# Dongle_charger.net
KiCad netlist of a schematic drawn in EAGLE
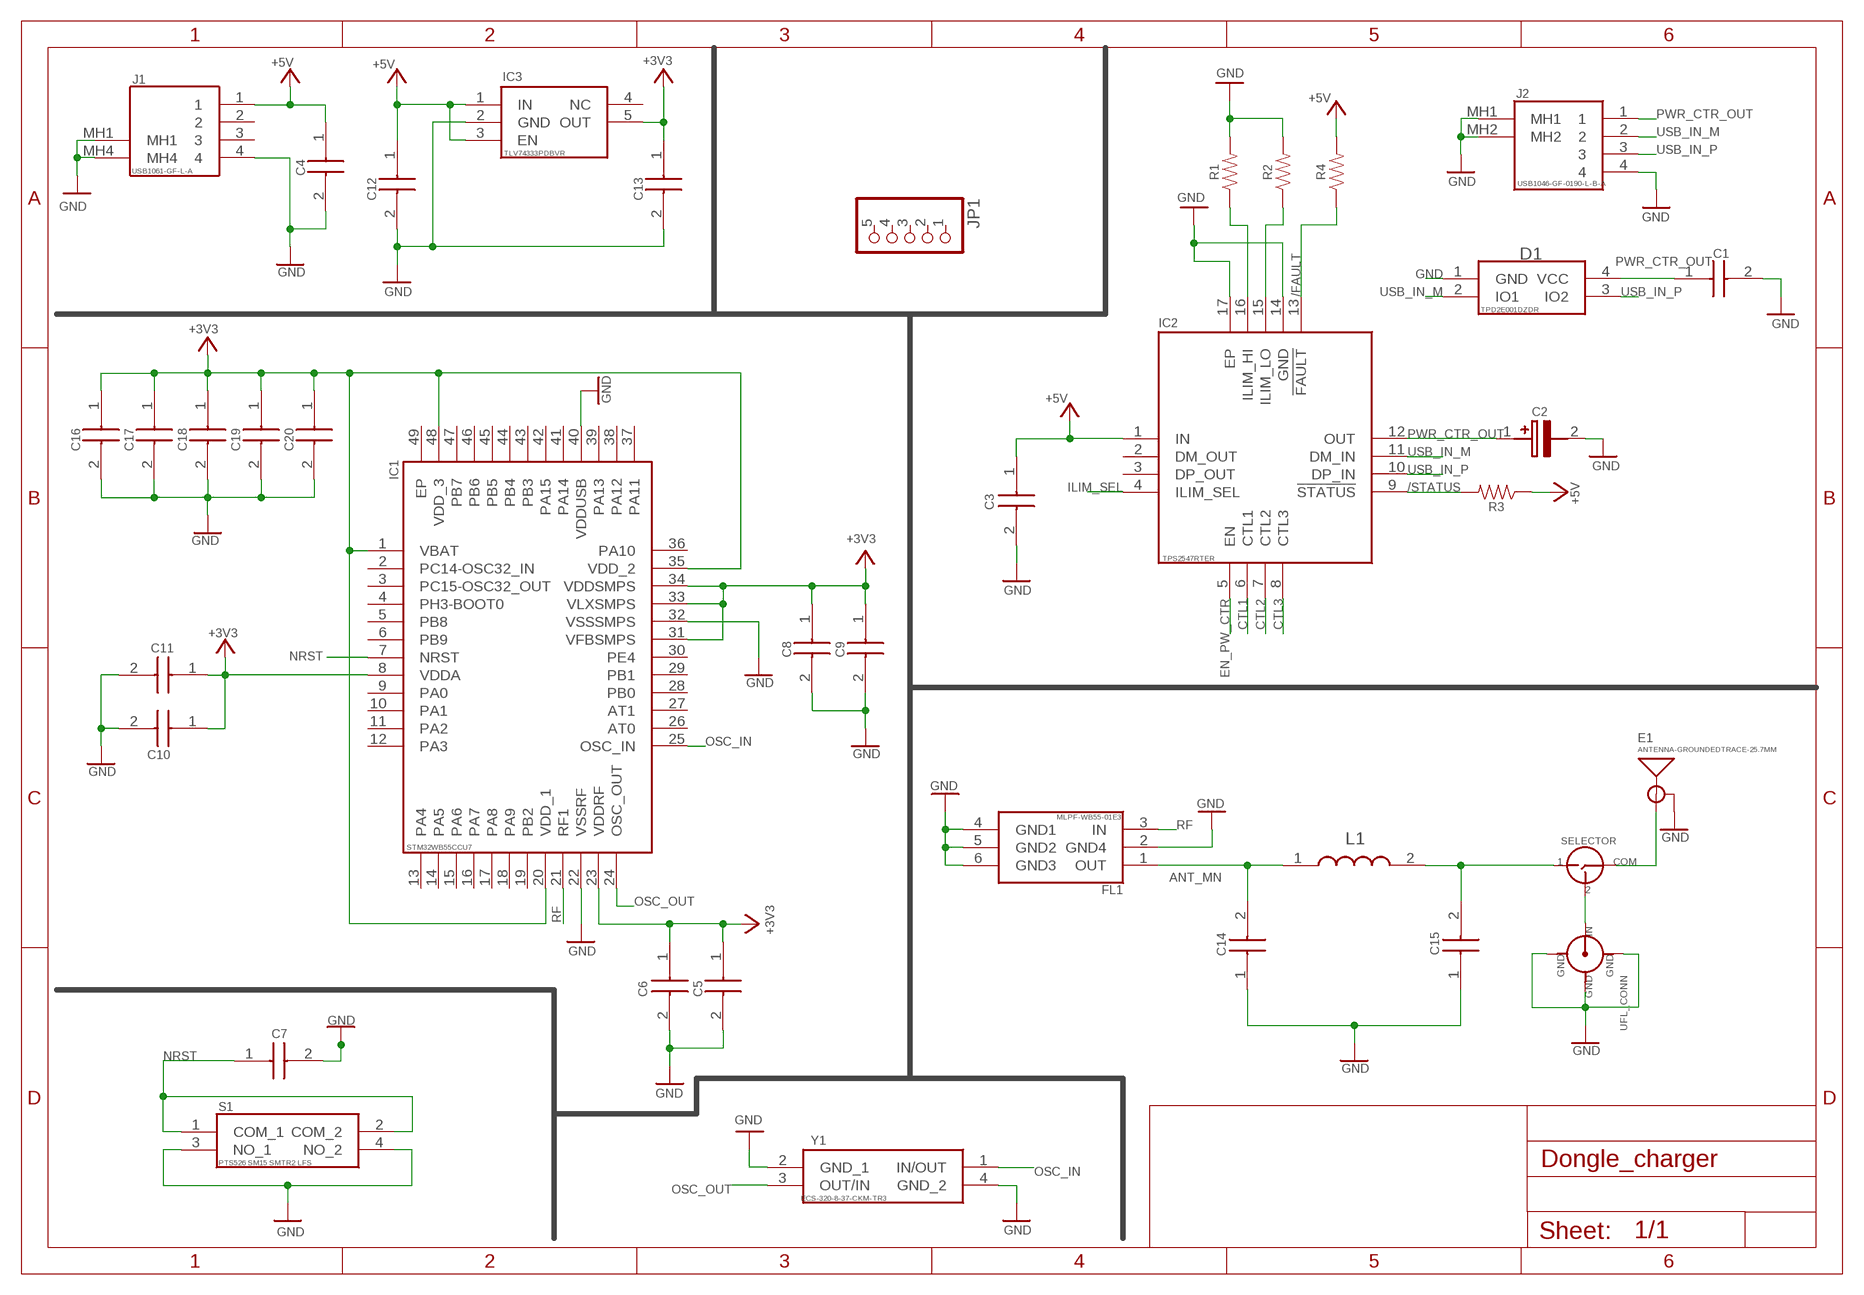
[diagram p0: schematic, sheet 1]

(export (version "E")
  (design (tool "Eeschema 10.0.6"))
  (components
    (comp (ref "C1")
      (value "0.1u")
      (footprint "eagle-import:CAPC1608X95N")
      (fields
        (field (name "MANUFACTURER_PART_NUMBER") "C0603C104K5RAC7867")
        (field (name "MOUSER_PART_NUMBER") "80-C0603C104K5R7867")
      )
      (libsource (lib "eagle-import") (part "C0603C104K5RAC7867"))
    )
    (comp (ref "C2")
      (value "150u")
      (footprint "eagle-import:CAPPM7344X310N")
      (fields (field (name "MANUFACTURER_PART_NUMBER") "TPSD157K010R0100"))
      (libsource (lib "eagle-import") (part "TPSD157K010R0100"))
    )
    (comp (ref "C3")
      (value "0.1u")
      (footprint "eagle-import:CAPC1608X95N")
      (fields
        (field (name "MANUFACTURER_PART_NUMBER") "C0603C104K5RAC7867")
        (field (name "MOUSER_PART_NUMBER") "80-C0603C104K5R7867")
      )
      (libsource (lib "eagle-import") (part "C0603C104K5RAC7867"))
    )
    (comp (ref "C4")
      (value "10u")
      (footprint "eagle-import:CAPC2012X140N")
      (fields
        (field (name "MANUFACTURER_PART_NUMBER") "CL21A106KOQNNNE")
        (field (name "MOUSER_PART_NUMBER") "187-CL21A106KOQNNNE")
      )
      (libsource (lib "eagle-import") (part "CL21A106KOQNNNE"))
    )
    (comp (ref "C5")
      (value "100p")
      (footprint "eagle-import:CAPC1005X55N")
      (fields
        (field (name "MANUFACTURER_PART_NUMBER") "885012205055")
        (field (name "MOUSER_PART_NUMBER") "710-885012205055")
      )
      (libsource (lib "eagle-import") (part "885012205055"))
    )
    (comp (ref "C6")
      (value "100n")
      (footprint "eagle-import:CAPPC1005X55N")
      (fields
        (field (name "MANUFACTURER_PART_NUMBER") "LMF105B7104MVHF")
        (field (name "MOUSER_PART_NUMBER") "963-LMF105B7104MVHF")
      )
      (libsource (lib "eagle-import") (part "LMF105B7104MVHF"))
    )
    (comp (ref "C7")
      (value "C0603C104K5RAC7867")
      (footprint "eagle-import:CAPC1608X95N")
      (fields (field (name "MOUSER_PART_NUMBER") "80-C0603C104K5R7867"))
      (libsource (lib "eagle-import") (part "C0603C104K5RAC7867"))
    )
    (comp (ref "C8")
      (value "4.7u")
      (footprint "eagle-import:CAPC1608X90N")
      (fields
        (field (name "MANUFACTURER_PART_NUMBER") "GRT188R6YA475KE13J")
        (field (name "MOUSER_PART_NUMBER") "81-GRT188R6YA475KE3J")
      )
      (libsource (lib "eagle-import") (part "GRT188R6YA475KE13J"))
    )
    (comp (ref "C9")
      (value "0.1u")
      (footprint "eagle-import:CAPC1608X95N")
      (fields
        (field (name "MANUFACTURER_PART_NUMBER") "C0603C104K5RAC7867")
        (field (name "MOUSER_PART_NUMBER") "80-C0603C104K5R7867")
      )
      (libsource (lib "eagle-import") (part "C0603C104K5RAC7867"))
    )
    (comp (ref "C10")
      (value "10n")
      (footprint "eagle-import:CAPC1608X80N")
      (fields
        (field (name "MANUFACTURER_PART_NUMBER") "C1608X5R1H103K080AA")
        (field (name "MOUSER_PART_NUMBER") "810-C1608X5R1H103KAA")
      )
      (libsource (lib "eagle-import") (part "C1608X5R1H103K080AA"))
    )
    (comp (ref "C11")
      (value "1u")
      (footprint "eagle-import:CAPC1608X90N")
      (fields
        (field (name "MANUFACTURER_PART_NUMBER") "CL10A105KA8NNNC")
        (field (name "MOUSER_PART_NUMBER") "187-CL10A105KA8NNNC")
      )
      (libsource (lib "eagle-import") (part "CL10A105KA8NNNC"))
    )
    (comp (ref "C12")
      (value "1u")
      (footprint "eagle-import:CAPC1608X95N")
      (fields
        (field (name "MANUFACTURER_PART_NUMBER") "C0603C105K3PAC")
        (field (name "MOUSER_PART_NUMBER") "80-C0603C105K3PAC")
      )
      (libsource (lib "eagle-import") (part "C0603C105K3PAC"))
    )
    (comp (ref "C13")
      (value "1u")
      (footprint "eagle-import:CAPC1608X95N")
      (fields
        (field (name "MANUFACTURER_PART_NUMBER") "C0603C105K3PAC")
        (field (name "MOUSER_PART_NUMBER") "80-C0603C105K3PAC")
      )
      (libsource (lib "eagle-import") (part "C0603C105K3PAC"))
    )
    (comp (ref "C14")
      (value "GCM1555G1H1R0CA16D")
      (footprint "eagle-import:CAPC1005X55N")
      (fields (field (name "MOUSER_PART_NUMBER") "81-GCM1555G1H1R0CA6D"))
      (libsource (lib "eagle-import") (part "GCM1555G1H1R0CA16D"))
    )
    (comp (ref "C15")
      (value "GCM1555G1H1R0CA16D")
      (footprint "eagle-import:CAPC1005X55N")
      (fields (field (name "MOUSER_PART_NUMBER") "81-GCM1555G1H1R0CA6D"))
      (libsource (lib "eagle-import") (part "GCM1555G1H1R0CA16D"))
    )
    (comp (ref "C16")
      (value "4.7u")
      (footprint "eagle-import:CAPC1608X90N")
      (fields
        (field (name "MANUFACTURER_PART_NUMBER") "GRT188R6YA475KE13J")
        (field (name "MOUSER_PART_NUMBER") "81-GRT188R6YA475KE3J")
      )
      (libsource (lib "eagle-import") (part "GRT188R6YA475KE13J"))
    )
    (comp (ref "C17")
      (value "0.1u")
      (footprint "eagle-import:CAPC1608X95N")
      (fields
        (field (name "MANUFACTURER_PART_NUMBER") "C0603C104K5RAC7867")
        (field (name "MOUSER_PART_NUMBER") "80-C0603C104K5R7867")
      )
      (libsource (lib "eagle-import") (part "C0603C104K5RAC7867"))
    )
    (comp (ref "C18")
      (value "0.1u")
      (footprint "eagle-import:CAPC1608X95N")
      (fields
        (field (name "MANUFACTURER_PART_NUMBER") "C0603C104K5RAC7867")
        (field (name "MOUSER_PART_NUMBER") "80-C0603C104K5R7867")
      )
      (libsource (lib "eagle-import") (part "C0603C104K5RAC7867"))
    )
    (comp (ref "C19")
      (value "0.1u")
      (footprint "eagle-import:CAPC1608X95N")
      (fields
        (field (name "MANUFACTURER_PART_NUMBER") "C0603C104K5RAC7867")
        (field (name "MOUSER_PART_NUMBER") "80-C0603C104K5R7867")
      )
      (libsource (lib "eagle-import") (part "C0603C104K5RAC7867"))
    )
    (comp (ref "C20")
      (value "0.1u")
      (footprint "eagle-import:CAPC1608X95N")
      (fields
        (field (name "MANUFACTURER_PART_NUMBER") "C0603C104K5RAC7867")
        (field (name "MOUSER_PART_NUMBER") "80-C0603C104K5R7867")
      )
      (libsource (lib "eagle-import") (part "C0603C104K5RAC7867"))
    )
    (comp (ref "D1")
      (value "TPD2E001DZDR")
      (footprint "eagle-import:TPD2E001DZDR")
      (fields
        (field (name "MANUFACTURER_PART_NUMBER") "TPD2E001DZDR")
        (field (name "MOUSER_PART_NUMBER") "595-TPD2E001DZDR")
      )
      (libsource (lib "eagle-import") (part "TPD2E001DZDR"))
    )
    (comp (ref "E1")
      (value "ANTENNA-GROUNDEDTRACE-25.7MM")
      (footprint "eagle-import:TRACE_ANTENNA_2.4GHZ_25.7MM")
      (libsource (lib "eagle-import") (part "ANTENNA-GROUNDEDTRACE-25.7MM"))
    )
    (comp (ref "FL1")
      (value "MLPF-WB55-01E3")
      (footprint "eagle-import:MLPFWB5501E3")
      (fields (field (name "MOUSER_PART_NUMBER") "511-MLPF-WB55-01E3"))
      (libsource (lib "eagle-import") (part "MLPF-WB55-01E3"))
    )
    (comp (ref "IC1")
      (value "STM32WB55CCU7")
      (footprint "eagle-import:QFN50P700X700X65-49N")
      (fields (field (name "MOUSER_PART_NUMBER") "511-STM32WB55CCU7") (field (name "SPICEPREFIX") "X"))
      (libsource (lib "eagle-import") (part "STM32WB55CCU7"))
    )
    (comp (ref "IC2")
      (value "TPS2547RTER")
      (footprint "eagle-import:QFN50P300X300X80-17N")
      (fields
        (field (name "MANUFACTURER_PART_NUMBER") "TPS2547RTER")
        (field (name "MOUSER_PART_NUMBER") "595-TPS2547RTER")
      )
      (libsource (lib "eagle-import") (part "TPS2547RTER"))
    )
    (comp (ref "IC3")
      (value "TLV74333PDBVR")
      (footprint "eagle-import:SOT95P280X145-5N")
      (fields (field (name "MOUSER_PART_NUMBER") "595-TLV74333PDBVR"))
      (libsource (lib "eagle-import") (part "TLV74333PDBVR"))
    )
    (comp (ref "J1")
      (value "USB1061-GF-L-A")
      (footprint "eagle-import:USB1061GFLA")
      (fields
        (field (name "MANUFACTURER_PART_NUMBER") "USB1061-GF-L-A")
        (field (name "MOUSER_PART_NUMBER") "640-USB1061-GF-L-A")
      )
      (libsource (lib "eagle-import") (part "USB1061-GF-L-A"))
    )
    (comp (ref "J2")
      (value "USB1046-GF-0190-L-B-A")
      (footprint "eagle-import:USB1046GF0190LBA")
      (fields
        (field (name "MANUFACTURER_PART_NUMBER") "USB1046-GF-0190-L-B-A")
        (field (name "MOUSER_PART_NUMBER") "640-USB1046GF0190LBA")
      )
      (libsource (lib "eagle-import") (part "USB1046-GF-0190-L-B-A"))
    )
    (comp (ref "JP1")
      (value "PINHD-1X5")
      (footprint "eagle-import:1X05")
      (libsource (lib "eagle-import") (part "PINHD-1X5"))
    )
    (comp (ref "L1")
      (value "ATFC-0402-2N5-BT")
      (footprint "eagle-import:INDC1005X37N")
      (fields (field (name "MOUSER_PART_NUMBER") "815-ATFC-0402-2N5-BT"))
      (libsource (lib "eagle-import") (part "ATFC-0402-2N5-BT"))
    )
    (comp (ref "R1")
      (value "16.9K")
      (footprint "eagle-import:0603")
      (libsource (lib "eagle-import") (part "1.8MOHM"))
    )
    (comp (ref "R2")
      (value "80.6K")
      (footprint "eagle-import:0603")
      (libsource (lib "eagle-import") (part "1.8MOHM"))
    )
    (comp (ref "R3")
      (value "80.6K")
      (footprint "eagle-import:0603")
      (libsource (lib "eagle-import") (part "1.8MOHM"))
    )
    (comp (ref "R4")
      (value "80.6K")
      (footprint "eagle-import:0603")
      (libsource (lib "eagle-import") (part "1.8MOHM"))
    )
    (comp (ref "S1")
      (value "PTS526_SM15_SMTR2_LFS")
      (footprint "eagle-import:PTS526SM15SMTR2LFS")
      (fields
        (field (name "MANUFACTURER_PART_NUMBER") "PTS526 SM15 SMTR2 LFS")
        (field (name "MOUSER_PART_NUMBER") "611-PTS526SM15SMTR2L")
      )
      (libsource (lib "eagle-import") (part "PTS526_SM15_SMTR2_LFS"))
    )
    (comp (ref "SEL1")
      (value "3_PIN_RES")
      (footprint "eagle-import:3_PAD_RES")
      (libsource (lib "eagle-import") (part "3_PIN_RES"))
    )
    (comp (ref "UFL1")
      (value "UFL_CONNECTOR")
      (footprint "eagle-import:UFL_CONNECTOR")
      (libsource (lib "eagle-import") (part "UFL_CONNECTOR"))
    )
    (comp (ref "Y1")
      (value "ECS-320-8-37-CKM-TR3")
      (footprint "eagle-import:ECS320837CKMTR3")
      (fields
        (field (name "MANUFACTURER_PART_NUMBER") "ECS-320-8-37-CKM-TR3")
        (field (name "MOUSER_PART_NUMBER") "520-ECS-320837CKMTR3")
      )
      (libsource (lib "eagle-import") (part "ECS-320-8-37-CKM-TR3"))
    )
  )
  (nets
    (net (code "1") (name "+3V3") (class "Default")
      (node (ref "C10") (pin "1") (pinfunction "1_1") (pintype "bidirectional"))
      (node (ref "C11") (pin "1") (pinfunction "1_1") (pintype "bidirectional"))
      (node (ref "C13") (pin "1") (pinfunction "1_1") (pintype "bidirectional"))
      (node (ref "C16") (pin "1") (pinfunction "1_1") (pintype "bidirectional"))
      (node (ref "C17") (pin "1") (pinfunction "1_1") (pintype "bidirectional"))
      (node (ref "C18") (pin "1") (pinfunction "1_1") (pintype "bidirectional"))
      (node (ref "C19") (pin "1") (pinfunction "1_1") (pintype "bidirectional"))
      (node (ref "C20") (pin "1") (pinfunction "1_1") (pintype "bidirectional"))
      (node (ref "C5") (pin "1") (pinfunction "1_1") (pintype "bidirectional"))
      (node (ref "C6") (pin "1") (pinfunction "+_1") (pintype "bidirectional"))
      (node (ref "C8") (pin "1") (pinfunction "1_1") (pintype "bidirectional"))
      (node (ref "C9") (pin "1") (pinfunction "1_1") (pintype "bidirectional"))
      (node (ref "IC1") (pin "1") (pinfunction "VBAT_1") (pintype "bidirectional"))
      (node (ref "IC1") (pin "20") (pinfunction "VDD_1_20") (pintype "bidirectional"))
      (node (ref "IC1") (pin "23") (pinfunction "VDDRF_23") (pintype "bidirectional"))
      (node (ref "IC1") (pin "31") (pinfunction "VFBSMPS_31") (pintype "bidirectional"))
      (node (ref "IC1") (pin "33") (pinfunction "VLXSMPS_33") (pintype "bidirectional"))
      (node (ref "IC1") (pin "34") (pinfunction "VDDSMPS_34") (pintype "bidirectional"))
      (node (ref "IC1") (pin "35") (pinfunction "VDD_2_35") (pintype "bidirectional"))
      (node (ref "IC1") (pin "48") (pinfunction "VDD_3_48") (pintype "bidirectional"))
      (node (ref "IC1") (pin "8") (pinfunction "VDDA_8") (pintype "bidirectional"))
      (node (ref "IC3") (pin "5") (pinfunction "OUT_5") (pintype "bidirectional"))
    )
    (net (code "2") (name "+5V") (class "Default")
      (node (ref "C12") (pin "1") (pinfunction "1_1") (pintype "bidirectional"))
      (node (ref "C3") (pin "1") (pinfunction "1_1") (pintype "bidirectional"))
      (node (ref "C4") (pin "1") (pinfunction "1_1") (pintype "bidirectional"))
      (node (ref "IC2") (pin "1") (pinfunction "IN_1") (pintype "bidirectional"))
      (node (ref "IC3") (pin "1") (pinfunction "IN_1") (pintype "bidirectional"))
      (node (ref "IC3") (pin "3") (pinfunction "EN_3") (pintype "bidirectional"))
      (node (ref "J1") (pin "1") (pinfunction "1_1") (pintype "bidirectional"))
      (node (ref "R3") (pin "1") (pinfunction "1_1") (pintype "passive"))
      (node (ref "R4") (pin "2") (pinfunction "2_2") (pintype "passive"))
    )
    (net (code "3") (name "/ANT_MN") (class "Default")
      (node (ref "C14") (pin "2") (pinfunction "2_2") (pintype "bidirectional"))
      (node (ref "FL1") (pin "1") (pinfunction "OUT_1") (pintype "bidirectional"))
      (node (ref "L1") (pin "1") (pinfunction "1_1") (pintype "bidirectional"))
    )
    (net (code "4") (name "/CTL1") (class "Default")
      (node (ref "IC2") (pin "6") (pinfunction "CTL1_6") (pintype "bidirectional"))
    )
    (net (code "5") (name "/CTL2") (class "Default")
      (node (ref "IC2") (pin "7") (pinfunction "CTL2_7") (pintype "bidirectional"))
    )
    (net (code "6") (name "/CTL3") (class "Default")
      (node (ref "IC2") (pin "8") (pinfunction "CTL3_8") (pintype "bidirectional"))
    )
    (net (code "7") (name "/EN_PW_CTR") (class "Default")
      (node (ref "IC2") (pin "5") (pinfunction "EN_5") (pintype "bidirectional"))
    )
    (net (code "8") (name "/ILIM_SEL") (class "Default")
      (node (ref "IC2") (pin "4") (pinfunction "ILIM_SEL_4") (pintype "bidirectional"))
    )
    (net (code "9") (name "/NRST") (class "Default")
      (node (ref "C7") (pin "1") (pinfunction "1_1") (pintype "bidirectional"))
      (node (ref "IC1") (pin "7") (pinfunction "NRST_7") (pintype "bidirectional"))
      (node (ref "S1") (pin "1") (pinfunction "COM_1_1") (pintype "bidirectional"))
      (node (ref "S1") (pin "2") (pinfunction "COM_2_2") (pintype "bidirectional"))
    )
    (net (code "10") (name "/OSC_IN") (class "Default")
      (node (ref "IC1") (pin "25") (pinfunction "OSC_IN_25") (pintype "bidirectional"))
      (node (ref "Y1") (pin "1") (pinfunction "IN/OUT_1") (pintype "bidirectional"))
    )
    (net (code "11") (name "/OSC_OUT") (class "Default")
      (node (ref "IC1") (pin "24") (pinfunction "OSC_OUT_24") (pintype "bidirectional"))
      (node (ref "Y1") (pin "3") (pinfunction "OUT/IN_3") (pintype "bidirectional"))
    )
    (net (code "12") (name "/PWR_CTR_OUT") (class "Default")
      (node (ref "C1") (pin "1") (pinfunction "1_1") (pintype "bidirectional"))
      (node (ref "C2") (pin "1") (pinfunction "+_1") (pintype "bidirectional"))
      (node (ref "D1") (pin "4") (pinfunction "VCC_4") (pintype "bidirectional"))
      (node (ref "IC2") (pin "12") (pinfunction "OUT_12") (pintype "bidirectional"))
      (node (ref "J2") (pin "1") (pinfunction "1_1") (pintype "bidirectional"))
    )
    (net (code "13") (name "/RF") (class "Default")
      (node (ref "FL1") (pin "3") (pinfunction "IN_3") (pintype "bidirectional"))
      (node (ref "IC1") (pin "21") (pinfunction "RF1_21") (pintype "bidirectional"))
    )
    (net (code "14") (name "/USB_IN_M") (class "Default")
      (node (ref "D1") (pin "2") (pinfunction "IO1_2") (pintype "bidirectional"))
      (node (ref "IC2") (pin "11") (pinfunction "DM_IN_11") (pintype "bidirectional"))
      (node (ref "J2") (pin "2") (pinfunction "2_2") (pintype "bidirectional"))
    )
    (net (code "15") (name "/USB_IN_P") (class "Default")
      (node (ref "D1") (pin "3") (pinfunction "IO2_3") (pintype "bidirectional"))
      (node (ref "IC2") (pin "10") (pinfunction "DP_IN_10") (pintype "bidirectional"))
      (node (ref "J2") (pin "3") (pinfunction "3_3") (pintype "bidirectional"))
    )
    (net (code "16") (name "/{slash}FAULT") (class "Default")
      (node (ref "IC2") (pin "13") (pinfunction "~{FAULT}_13") (pintype "bidirectional"))
      (node (ref "R4") (pin "1") (pinfunction "1_1") (pintype "passive"))
    )
    (net (code "17") (name "/{slash}STATUS") (class "Default")
      (node (ref "IC2") (pin "9") (pinfunction "~{STATUS}_9") (pintype "bidirectional"))
      (node (ref "R3") (pin "2") (pinfunction "2_2") (pintype "passive"))
    )
    (net (code "18") (name "GND") (class "Default")
      (node (ref "C1") (pin "2") (pinfunction "2_2") (pintype "bidirectional"))
      (node (ref "C10") (pin "2") (pinfunction "2_2") (pintype "bidirectional"))
      (node (ref "C11") (pin "2") (pinfunction "2_2") (pintype "bidirectional"))
      (node (ref "C12") (pin "2") (pinfunction "2_2") (pintype "bidirectional"))
      (node (ref "C13") (pin "2") (pinfunction "2_2") (pintype "bidirectional"))
      (node (ref "C14") (pin "1") (pinfunction "1_1") (pintype "bidirectional"))
      (node (ref "C15") (pin "1") (pinfunction "1_1") (pintype "bidirectional"))
      (node (ref "C16") (pin "2") (pinfunction "2_2") (pintype "bidirectional"))
      (node (ref "C17") (pin "2") (pinfunction "2_2") (pintype "bidirectional"))
      (node (ref "C18") (pin "2") (pinfunction "2_2") (pintype "bidirectional"))
      (node (ref "C19") (pin "2") (pinfunction "2_2") (pintype "bidirectional"))
      (node (ref "C2") (pin "2") (pinfunction "-_2") (pintype "bidirectional"))
      (node (ref "C20") (pin "2") (pinfunction "2_2") (pintype "bidirectional"))
      (node (ref "C3") (pin "2") (pinfunction "2_2") (pintype "bidirectional"))
      (node (ref "C4") (pin "2") (pinfunction "2_2") (pintype "bidirectional"))
      (node (ref "C5") (pin "2") (pinfunction "2_2") (pintype "bidirectional"))
      (node (ref "C6") (pin "2") (pinfunction "-_2") (pintype "bidirectional"))
      (node (ref "C7") (pin "2") (pinfunction "2_2") (pintype "bidirectional"))
      (node (ref "C8") (pin "2") (pinfunction "2_2") (pintype "bidirectional"))
      (node (ref "C9") (pin "2") (pinfunction "2_2") (pintype "bidirectional"))
      (node (ref "D1") (pin "1") (pinfunction "GND_1") (pintype "bidirectional"))
      (node (ref "E1") (pin "GND") (pinfunction "GND_GND") (pintype "bidirectional"))
      (node (ref "E1") (pin "GND2") (pinfunction "GND_GND2") (pintype "bidirectional"))
      (node (ref "FL1") (pin "2") (pinfunction "GND4_2") (pintype "bidirectional"))
      (node (ref "FL1") (pin "4") (pinfunction "GND1_4") (pintype "bidirectional"))
      (node (ref "FL1") (pin "5") (pinfunction "GND2_5") (pintype "bidirectional"))
      (node (ref "FL1") (pin "6") (pinfunction "GND3_6") (pintype "bidirectional"))
      (node (ref "IC1") (pin "22") (pinfunction "VSSRF_22") (pintype "bidirectional"))
      (node (ref "IC1") (pin "32") (pinfunction "VSSSMPS_32") (pintype "bidirectional"))
      (node (ref "IC1") (pin "40") (pinfunction "VDDUSB_40") (pintype "bidirectional"))
      (node (ref "IC2") (pin "14") (pinfunction "GND_14") (pintype "bidirectional"))
      (node (ref "IC2") (pin "17") (pinfunction "EP_17") (pintype "bidirectional"))
      (node (ref "IC3") (pin "2") (pinfunction "GND_2") (pintype "bidirectional"))
      (node (ref "J1") (pin "4") (pinfunction "4_4") (pintype "bidirectional"))
      (node (ref "J1") (pin "MH1") (pinfunction "MH1_MH1") (pintype "bidirectional"))
      (node (ref "J1") (pin "MH4") (pinfunction "MH4_MH4") (pintype "bidirectional"))
      (node (ref "J2") (pin "4") (pinfunction "4_4") (pintype "bidirectional"))
      (node (ref "J2") (pin "MH1") (pinfunction "MH1_MH1") (pintype "bidirectional"))
      (node (ref "J2") (pin "MH2") (pinfunction "MH2_MH2") (pintype "bidirectional"))
      (node (ref "R1") (pin "2") (pinfunction "2_2") (pintype "passive"))
      (node (ref "R2") (pin "2") (pinfunction "2_2") (pintype "passive"))
      (node (ref "S1") (pin "3") (pinfunction "NO_1_3") (pintype "bidirectional"))
      (node (ref "S1") (pin "4") (pinfunction "NO_2_4") (pintype "bidirectional"))
      (node (ref "UFL1") (pin "1") (pinfunction "1_1") (pintype "bidirectional"))
      (node (ref "UFL1") (pin "2") (pinfunction "2_2") (pintype "bidirectional"))
      (node (ref "UFL1") (pin "3") (pinfunction "3_3") (pintype "bidirectional"))
      (node (ref "Y1") (pin "2") (pinfunction "GND_1_2") (pintype "bidirectional"))
      (node (ref "Y1") (pin "4") (pinfunction "GND_2_4") (pintype "bidirectional"))
    )
    (net (code "19") (name "Net-(C15-Pad2)") (class "Default")
      (node (ref "C15") (pin "2") (pinfunction "2_2") (pintype "bidirectional"))
      (node (ref "L1") (pin "2") (pinfunction "2_2") (pintype "bidirectional"))
      (node (ref "SEL1") (pin "1") (pinfunction "1_1") (pintype "bidirectional"))
    )
    (net (code "20") (name "Net-(E1-SIGNAL)") (class "Default")
      (node (ref "E1") (pin "ANT") (pinfunction "SIGNAL_ANT") (pintype "bidirectional"))
      (node (ref "SEL1") (pin "COM") (pinfunction "COM_COM") (pintype "bidirectional"))
    )
    (net (code "21") (name "Net-(IC2-ILIM_HI)") (class "Default")
      (node (ref "IC2") (pin "16") (pinfunction "ILIM_HI_16") (pintype "bidirectional"))
      (node (ref "R1") (pin "1") (pinfunction "1_1") (pintype "passive"))
    )
    (net (code "22") (name "Net-(IC2-ILIM_LO)") (class "Default")
      (node (ref "IC2") (pin "15") (pinfunction "ILIM_LO_15") (pintype "bidirectional"))
      (node (ref "R2") (pin "1") (pinfunction "1_1") (pintype "passive"))
    )
    (net (code "23") (name "Net-(SEL1-Pad2)") (class "Default")
      (node (ref "SEL1") (pin "2") (pinfunction "2_2") (pintype "bidirectional"))
      (node (ref "UFL1") (pin "IN") (pinfunction "IN_IN") (pintype "bidirectional"))
    )
    (net (code "24") (name "unconnected-(IC1-AT0-Pad26)") (class "Default")
      (node (ref "IC1") (pin "26") (pinfunction "AT0_26") (pintype "bidirectional"))
    )
    (net (code "25") (name "unconnected-(IC1-AT1-Pad27)") (class "Default")
      (node (ref "IC1") (pin "27") (pinfunction "AT1_27") (pintype "bidirectional"))
    )
    (net (code "26") (name "unconnected-(IC1-EP-Pad49)") (class "Default")
      (node (ref "IC1") (pin "49") (pinfunction "EP_49") (pintype "bidirectional"))
    )
    (net (code "27") (name "unconnected-(IC1-PA0-Pad9)") (class "Default")
      (node (ref "IC1") (pin "9") (pinfunction "PA0_9") (pintype "bidirectional"))
    )
    (net (code "28") (name "unconnected-(IC1-PA1-Pad10)") (class "Default")
      (node (ref "IC1") (pin "10") (pinfunction "PA1_10") (pintype "bidirectional"))
    )
    (net (code "29") (name "unconnected-(IC1-PA2-Pad11)") (class "Default")
      (node (ref "IC1") (pin "11") (pinfunction "PA2_11") (pintype "bidirectional"))
    )
    (net (code "30") (name "unconnected-(IC1-PA3-Pad12)") (class "Default")
      (node (ref "IC1") (pin "12") (pinfunction "PA3_12") (pintype "bidirectional"))
    )
    (net (code "31") (name "unconnected-(IC1-PA4-Pad13)") (class "Default")
      (node (ref "IC1") (pin "13") (pinfunction "PA4_13") (pintype "bidirectional"))
    )
    (net (code "32") (name "unconnected-(IC1-PA5-Pad14)") (class "Default")
      (node (ref "IC1") (pin "14") (pinfunction "PA5_14") (pintype "bidirectional"))
    )
    (net (code "33") (name "unconnected-(IC1-PA6-Pad15)") (class "Default")
      (node (ref "IC1") (pin "15") (pinfunction "PA6_15") (pintype "bidirectional"))
    )
    (net (code "34") (name "unconnected-(IC1-PA7-Pad16)") (class "Default")
      (node (ref "IC1") (pin "16") (pinfunction "PA7_16") (pintype "bidirectional"))
    )
    (net (code "35") (name "unconnected-(IC1-PA8-Pad17)") (class "Default")
      (node (ref "IC1") (pin "17") (pinfunction "PA8_17") (pintype "bidirectional"))
    )
    (net (code "36") (name "unconnected-(IC1-PA9-Pad18)") (class "Default")
      (node (ref "IC1") (pin "18") (pinfunction "PA9_18") (pintype "bidirectional"))
    )
    (net (code "37") (name "unconnected-(IC1-PA10-Pad36)") (class "Default")
      (node (ref "IC1") (pin "36") (pinfunction "PA10_36") (pintype "bidirectional"))
    )
    (net (code "38") (name "unconnected-(IC1-PA11-Pad37)") (class "Default")
      (node (ref "IC1") (pin "37") (pinfunction "PA11_37") (pintype "bidirectional"))
    )
    (net (code "39") (name "unconnected-(IC1-PA12-Pad38)") (class "Default")
      (node (ref "IC1") (pin "38") (pinfunction "PA12_38") (pintype "bidirectional"))
    )
    (net (code "40") (name "unconnected-(IC1-PA13-Pad39)") (class "Default")
      (node (ref "IC1") (pin "39") (pinfunction "PA13_39") (pintype "bidirectional"))
    )
    (net (code "41") (name "unconnected-(IC1-PA14-Pad41)") (class "Default")
      (node (ref "IC1") (pin "41") (pinfunction "PA14_41") (pintype "bidirectional"))
    )
    (net (code "42") (name "unconnected-(IC1-PA15-Pad42)") (class "Default")
      (node (ref "IC1") (pin "42") (pinfunction "PA15_42") (pintype "bidirectional"))
    )
    (net (code "43") (name "unconnected-(IC1-PB0-Pad28)") (class "Default")
      (node (ref "IC1") (pin "28") (pinfunction "PB0_28") (pintype "bidirectional"))
    )
    (net (code "44") (name "unconnected-(IC1-PB1-Pad29)") (class "Default")
      (node (ref "IC1") (pin "29") (pinfunction "PB1_29") (pintype "bidirectional"))
    )
    (net (code "45") (name "unconnected-(IC1-PB2-Pad19)") (class "Default")
      (node (ref "IC1") (pin "19") (pinfunction "PB2_19") (pintype "bidirectional"))
    )
    (net (code "46") (name "unconnected-(IC1-PB3-Pad43)") (class "Default")
      (node (ref "IC1") (pin "43") (pinfunction "PB3_43") (pintype "bidirectional"))
    )
    (net (code "47") (name "unconnected-(IC1-PB4-Pad44)") (class "Default")
      (node (ref "IC1") (pin "44") (pinfunction "PB4_44") (pintype "bidirectional"))
    )
    (net (code "48") (name "unconnected-(IC1-PB5-Pad45)") (class "Default")
      (node (ref "IC1") (pin "45") (pinfunction "PB5_45") (pintype "bidirectional"))
    )
    (net (code "49") (name "unconnected-(IC1-PB6-Pad46)") (class "Default")
      (node (ref "IC1") (pin "46") (pinfunction "PB6_46") (pintype "bidirectional"))
    )
    (net (code "50") (name "unconnected-(IC1-PB7-Pad47)") (class "Default")
      (node (ref "IC1") (pin "47") (pinfunction "PB7_47") (pintype "bidirectional"))
    )
    (net (code "51") (name "unconnected-(IC1-PB8-Pad5)") (class "Default")
      (node (ref "IC1") (pin "5") (pinfunction "PB8_5") (pintype "bidirectional"))
    )
    (net (code "52") (name "unconnected-(IC1-PB9-Pad6)") (class "Default")
      (node (ref "IC1") (pin "6") (pinfunction "PB9_6") (pintype "bidirectional"))
    )
    (net (code "53") (name "unconnected-(IC1-PC14-OSC32_IN-Pad2)") (class "Default")
      (node (ref "IC1") (pin "2") (pinfunction "PC14-OSC32_IN_2") (pintype "bidirectional"))
    )
    (net (code "54") (name "unconnected-(IC1-PC15-OSC32_OUT-Pad3)") (class "Default")
      (node (ref "IC1") (pin "3") (pinfunction "PC15-OSC32_OUT_3") (pintype "bidirectional"))
    )
    (net (code "55") (name "unconnected-(IC1-PE4-Pad30)") (class "Default")
      (node (ref "IC1") (pin "30") (pinfunction "PE4_30") (pintype "bidirectional"))
    )
    (net (code "56") (name "unconnected-(IC1-PH3-BOOT0-Pad4)") (class "Default")
      (node (ref "IC1") (pin "4") (pinfunction "PH3-BOOT0_4") (pintype "bidirectional"))
    )
    (net (code "57") (name "unconnected-(IC2-DM_OUT-Pad2)") (class "Default")
      (node (ref "IC2") (pin "2") (pinfunction "DM_OUT_2") (pintype "bidirectional"))
    )
    (net (code "58") (name "unconnected-(IC2-DP_OUT-Pad3)") (class "Default")
      (node (ref "IC2") (pin "3") (pinfunction "DP_OUT_3") (pintype "bidirectional"))
    )
    (net (code "59") (name "unconnected-(IC3-NC-Pad4)") (class "Default")
      (node (ref "IC3") (pin "4") (pinfunction "NC_4") (pintype "no_connect"))
    )
    (net (code "60") (name "unconnected-(J1-Pad2)") (class "Default")
      (node (ref "J1") (pin "2") (pinfunction "2_2") (pintype "bidirectional"))
    )
    (net (code "61") (name "unconnected-(J1-Pad3)") (class "Default")
      (node (ref "J1") (pin "3") (pinfunction "3_3") (pintype "bidirectional"))
    )
    (net (code "62") (name "unconnected-(JP1-Pad1)") (class "Default")
      (node (ref "JP1") (pin "1") (pinfunction "1_1") (pintype "passive"))
    )
    (net (code "63") (name "unconnected-(JP1-Pad2)") (class "Default")
      (node (ref "JP1") (pin "2") (pinfunction "2_2") (pintype "passive"))
    )
    (net (code "64") (name "unconnected-(JP1-Pad3)") (class "Default")
      (node (ref "JP1") (pin "3") (pinfunction "3_3") (pintype "passive"))
    )
    (net (code "65") (name "unconnected-(JP1-Pad4)") (class "Default")
      (node (ref "JP1") (pin "4") (pinfunction "4_4") (pintype "passive"))
    )
    (net (code "66") (name "unconnected-(JP1-Pad5)") (class "Default")
      (node (ref "JP1") (pin "5") (pinfunction "5_5") (pintype "passive"))
    )
  )
)
